# FTDI-support.net
KiCad netlist of a schematic drawn in Altium Designer
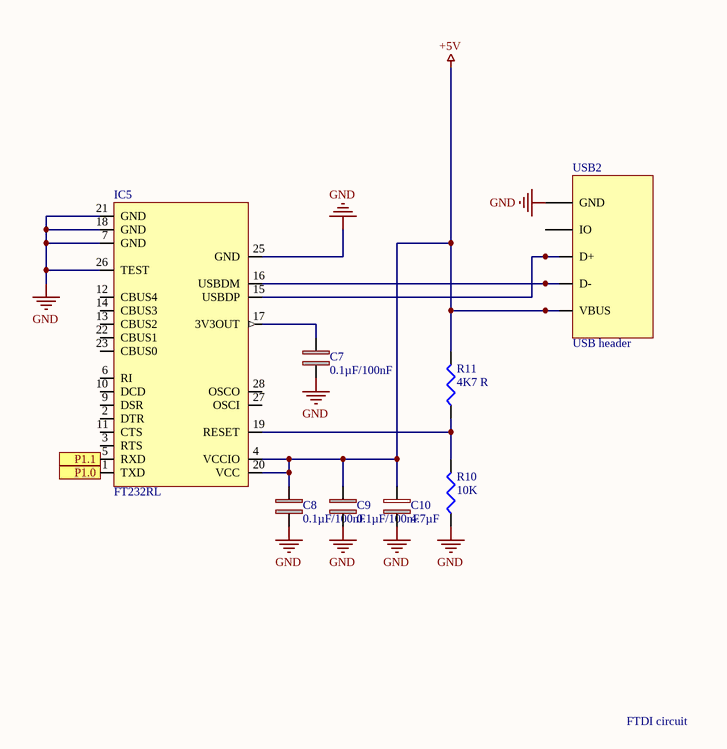
[diagram p0: FTDI-support.SchDoc]

(export (version "E")
  (design (tool "Eeschema 10.0.6"))
  (components
    (comp (ref "C7")
      (value "0.1µF/100nF")
      (footprint "MC0603B104K250CT")
      (description "Cap Ceramic 0.1uF 25V X7R 10% Pad SMD 0603 125C T/R")
      (fields
        (field (name "MANUFACTURER") "Multicomp")
        (field (name "MANUFACTURER PART NUMBER") "MC0603B104K250CT")
      )
      (libsource (lib "Tama_Schlib") (part "MC0603B104K250CT"))
    )
    (comp (ref "C8")
      (value "0.1µF/100nF")
      (footprint "MC0603B104K250CT")
      (description "Cap Ceramic 0.1uF 25V X7R 10% Pad SMD 0603 125C T/R")
      (fields
        (field (name "MANUFACTURER") "Multicomp")
        (field (name "MANUFACTURER PART NUMBER") "MC0603B104K250CT")
      )
      (libsource (lib "Tama_Schlib") (part "MC0603B104K250CT"))
    )
    (comp (ref "C9")
      (value "0.1µF/100nF")
      (footprint "MC0603B104K250CT")
      (description "Cap Ceramic 0.1uF 25V X7R 10% Pad SMD 0603 125C T/R")
      (fields
        (field (name "MANUFACTURER") "Multicomp")
        (field (name "MANUFACTURER PART NUMBER") "MC0603B104K250CT")
      )
      (libsource (lib "Tama_Schlib") (part "MC0603B104K250CT"))
    )
    (comp (ref "C10")
      (value "4.7µF")
      (footprint "TMCUA1C475KTRF")
      (description "Cap Tant Solid 4.7uF 16V UA CASE 10% (3.2 X 1.6 X 1.2mm) Inward L SMD 3216-12 4 Ohm 125C T/R")
      (fields
        (field (name "MANUFACTURER") "Vishay")
        (field (name "MANUFACTURER PART NUMBER") "TMCUA1C475KTRF")
      )
      (libsource (lib "Tama_Schlib") (part "TMCUA1C475KTRF"))
    )
    (comp (ref "IC5")
      (value "FT232RL")
      (footprint "SSOP28")
      (description "Usb Interface Ics Usb to Serial Uart 28 Pin SSOP")
      (fields (field (name "MANUFACTURER") "FTDI") (field (name "VOLTAGE") "5V"))
      (libsource (lib "Tama_Schlib") (part "FT232RL"))
    )
    (comp (ref "R10")
      (value "10K")
      (footprint "RC0805")
      (description "Res SMD 0805 10K 1% 0.125W T.C.100PPM")
      (fields
        (field (name "MANUFACTURER") "Yageo")
        (field (name "MANUFACTURER PART NUMBER") "RC0805FR-0710KL")
      )
      (libsource (lib "Tama_Schlib") (part "RC0805FR-0710KL"))
    )
    (comp (ref "R11")
      (value "4K7 R")
      (footprint "PCF0603")
      (description "Surface Mount Metal Film Resistor, Pcf Series, 4.7 Kohm, 63 Mw, - 0.1%, 75 V Rohs Compliant: Yes")
      (fields
        (field (name "MANUFACTURER") "TT Welwyn")
        (field (name "MANUFACTURER PART NUMBER") "PCF0603P-R-4K7-BT1")
      )
      (libsource (lib "Tama_Schlib") (part "PCF0603P-R-4K7-BT1"))
    )
    (comp (ref "USB2")
      (value "USB header")
      (footprint "Micro USB - Type B")
      (description "CONN HEADER 4 POS 2.54")
      (fields
        (field (name "MANUFACTURER") "Wurth Electronics")
        (field (name "MANUFACTURER PART NUMBER") "61300411121")
      )
      (libsource (lib "Tama_Schlib") (part "61300411121"))
    )
  )
  (nets
    (net (code "1") (name "+5V") (class "Default")
      (node (ref "C10") (pin "2") (pinfunction "+_2") (pintype "passive"))
      (node (ref "C8") (pin "1") (pinfunction "1_1") (pintype "passive"))
      (node (ref "C9") (pin "1") (pinfunction "1_1") (pintype "passive"))
      (node (ref "IC5") (pin "20") (pinfunction "VCC_20") (pintype "passive"))
      (node (ref "IC5") (pin "4") (pinfunction "VCCIO_4") (pintype "passive"))
      (node (ref "R11") (pin "2") (pinfunction "2_2") (pintype "passive"))
      (node (ref "USB2") (pin "1") (pinfunction "VBUS_1") (pintype "passive"))
    )
    (net (code "2") (name "/P1.0") (class "Default")
      (node (ref "IC5") (pin "1") (pinfunction "TXD_1") (pintype "passive"))
    )
    (net (code "3") (name "/P1.1") (class "Default")
      (node (ref "IC5") (pin "5") (pinfunction "RXD_5") (pintype "passive"))
    )
    (net (code "4") (name "GND") (class "Default")
      (node (ref "C10") (pin "1") (pinfunction "1_1") (pintype "passive"))
      (node (ref "C7") (pin "2") (pinfunction "2_2") (pintype "passive"))
      (node (ref "C8") (pin "2") (pinfunction "2_2") (pintype "passive"))
      (node (ref "C9") (pin "2") (pinfunction "2_2") (pintype "passive"))
      (node (ref "IC5") (pin "18") (pinfunction "GND_18") (pintype "passive"))
      (node (ref "IC5") (pin "21") (pinfunction "GND_21") (pintype "passive"))
      (node (ref "IC5") (pin "25") (pinfunction "GND_25") (pintype "passive"))
      (node (ref "IC5") (pin "26") (pinfunction "TEST_26") (pintype "passive"))
      (node (ref "IC5") (pin "7") (pinfunction "GND_7") (pintype "passive"))
      (node (ref "R10") (pin "1") (pinfunction "1_1") (pintype "passive"))
      (node (ref "USB2") (pin "5") (pinfunction "GND_5") (pintype "passive"))
    )
    (net (code "5") (name "Net-(IC5-3V3OUT)") (class "Default")
      (node (ref "C7") (pin "1") (pinfunction "1_1") (pintype "passive"))
      (node (ref "IC5") (pin "17") (pinfunction "3V3OUT_17") (pintype "output"))
    )
    (net (code "6") (name "Net-(IC5-RESET)") (class "Default")
      (node (ref "IC5") (pin "19") (pinfunction "RESET_19") (pintype "passive"))
      (node (ref "R10") (pin "2") (pinfunction "2_2") (pintype "passive"))
      (node (ref "R11") (pin "1") (pinfunction "1_1") (pintype "passive"))
    )
    (net (code "7") (name "Net-(IC5-USBDM)") (class "Default")
      (node (ref "IC5") (pin "16") (pinfunction "USBDM_16") (pintype "passive"))
      (node (ref "USB2") (pin "2") (pinfunction "D-_2") (pintype "passive"))
    )
    (net (code "8") (name "Net-(IC5-USBDP)") (class "Default")
      (node (ref "IC5") (pin "15") (pinfunction "USBDP_15") (pintype "passive"))
      (node (ref "USB2") (pin "3") (pinfunction "D+_3") (pintype "passive"))
    )
    (net (code "9") (name "unconnected-(IC5-CBUS0-Pad23)") (class "Default")
      (node (ref "IC5") (pin "23") (pinfunction "CBUS0_23") (pintype "passive"))
    )
    (net (code "10") (name "unconnected-(IC5-CBUS1-Pad22)") (class "Default")
      (node (ref "IC5") (pin "22") (pinfunction "CBUS1_22") (pintype "passive"))
    )
    (net (code "11") (name "unconnected-(IC5-CBUS2-Pad13)") (class "Default")
      (node (ref "IC5") (pin "13") (pinfunction "CBUS2_13") (pintype "passive"))
    )
    (net (code "12") (name "unconnected-(IC5-CBUS3-Pad14)") (class "Default")
      (node (ref "IC5") (pin "14") (pinfunction "CBUS3_14") (pintype "passive"))
    )
    (net (code "13") (name "unconnected-(IC5-CBUS4-Pad12)") (class "Default")
      (node (ref "IC5") (pin "12") (pinfunction "CBUS4_12") (pintype "passive"))
    )
    (net (code "14") (name "unconnected-(IC5-CTS-Pad11)") (class "Default")
      (node (ref "IC5") (pin "11") (pinfunction "CTS_11") (pintype "passive"))
    )
    (net (code "15") (name "unconnected-(IC5-DCD-Pad10)") (class "Default")
      (node (ref "IC5") (pin "10") (pinfunction "DCD_10") (pintype "passive"))
    )
    (net (code "16") (name "unconnected-(IC5-DSR-Pad9)") (class "Default")
      (node (ref "IC5") (pin "9") (pinfunction "DSR_9") (pintype "passive"))
    )
    (net (code "17") (name "unconnected-(IC5-DTR-Pad2)") (class "Default")
      (node (ref "IC5") (pin "2") (pinfunction "DTR_2") (pintype "passive"))
    )
    (net (code "18") (name "unconnected-(IC5-OSCI-Pad27)") (class "Default")
      (node (ref "IC5") (pin "27") (pinfunction "OSCI_27") (pintype "passive"))
    )
    (net (code "19") (name "unconnected-(IC5-OSCO-Pad28)") (class "Default")
      (node (ref "IC5") (pin "28") (pinfunction "OSCO_28") (pintype "passive"))
    )
    (net (code "20") (name "unconnected-(IC5-RI-Pad6)") (class "Default")
      (node (ref "IC5") (pin "6") (pinfunction "RI_6") (pintype "passive"))
    )
    (net (code "21") (name "unconnected-(IC5-RTS-Pad3)") (class "Default")
      (node (ref "IC5") (pin "3") (pinfunction "RTS_3") (pintype "passive"))
    )
    (net (code "22") (name "unconnected-(USB2-IO-Pad4)") (class "Default")
      (node (ref "USB2") (pin "4") (pinfunction "IO_4") (pintype "passive"))
    )
  )
)
